# GasSensor.net
KiCad netlist of a schematic drawn in Altium Designer
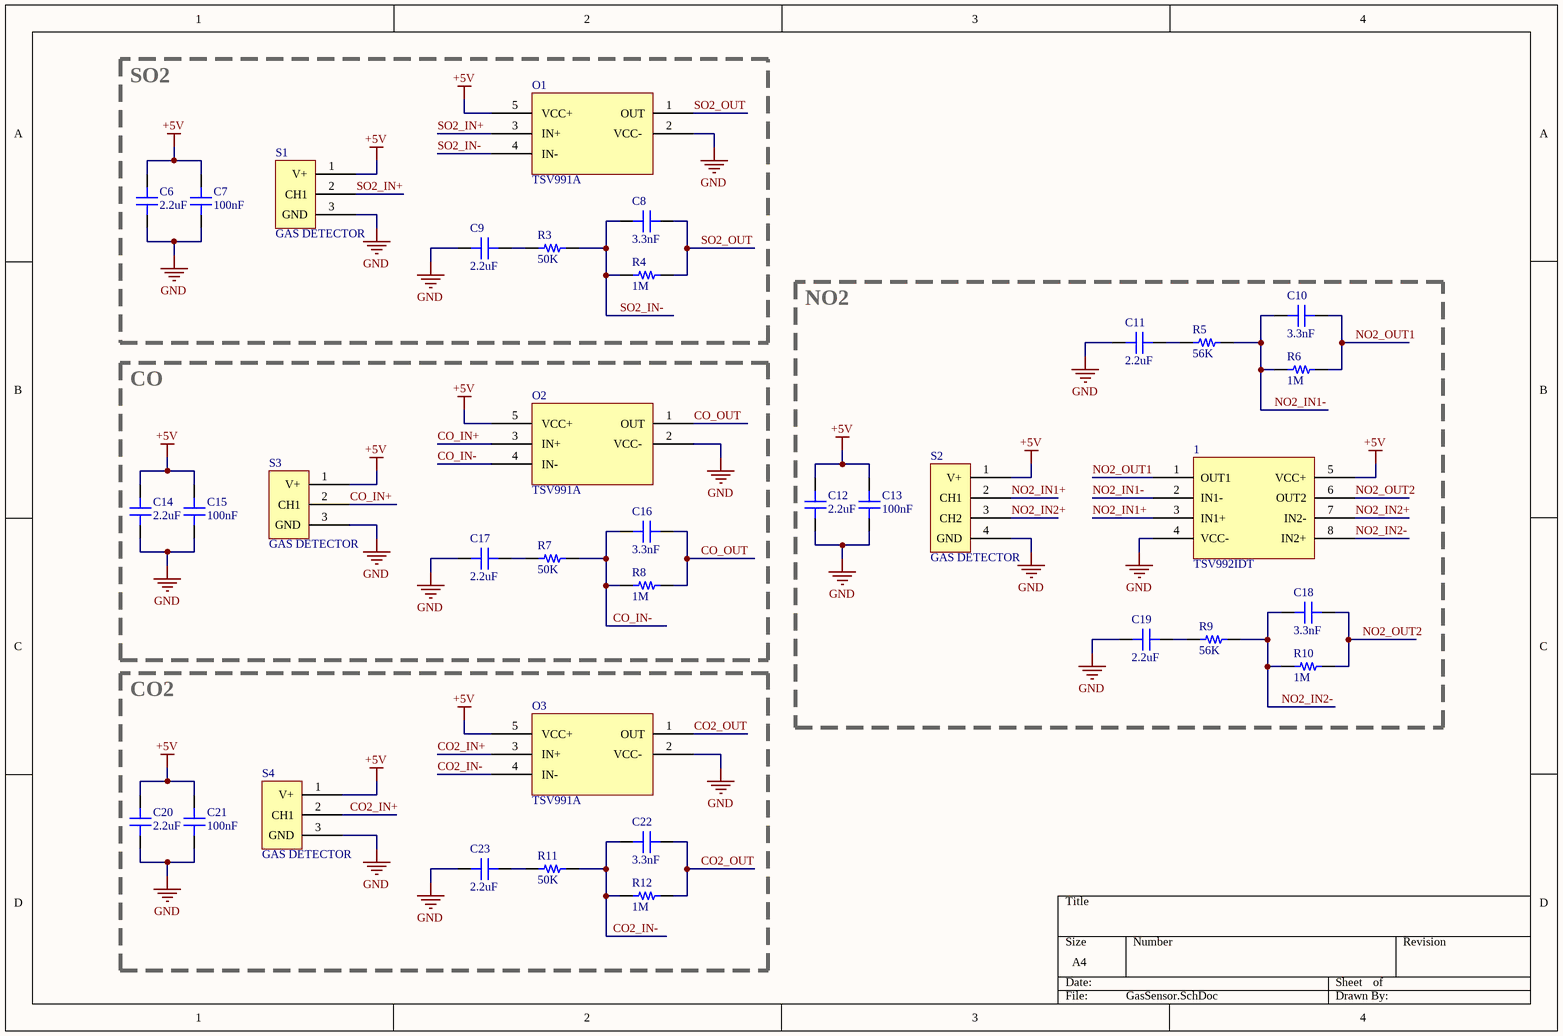
[diagram p0: GasSensor.SchDoc]

(export (version "E")
  (design (tool "Eeschema 10.0.6"))
  (components
    (comp (ref "1")
      (value "TSV992IDT")
      (footprint "SOIC8")
      (description "Operational Amplifiers Op Amps SOIC-8 2 Channel 20 MHz")
      (libsource (lib "hava_kalitesi_olcumu") (part "TSV992IDT"))
    )
    (comp (ref "C6")
      (value "2.2uF")
      (footprint "CAP 0603_1608")
      (description "CERAMİC 1206 SMD")
      (libsource (lib "hava_kalitesi_olcumu") (part "2.2uF"))
    )
    (comp (ref "C7")
      (value "100nF")
      (footprint "CAP 0603_1608")
      (description "CERAMİC 1206 SMD")
      (libsource (lib "hava_kalitesi_olcumu") (part "100nF"))
    )
    (comp (ref "C8")
      (value "3.3nF")
      (footprint "CAP 0603_1608")
      (description "CERAMİC 1206 SMD")
      (libsource (lib "hava_kalitesi_olcumu") (part "3.3nF"))
    )
    (comp (ref "C9")
      (value "2.2uF")
      (footprint "CAP 0603_1608")
      (description "CERAMİC 1206 SMD")
      (libsource (lib "hava_kalitesi_olcumu") (part "2.2uF"))
    )
    (comp (ref "C10")
      (value "3.3nF")
      (footprint "CAP 0603_1608")
      (description "CERAMİC 1206 SMD")
      (libsource (lib "hava_kalitesi_olcumu") (part "3.3nF"))
    )
    (comp (ref "C11")
      (value "2.2uF")
      (footprint "CAP 0603_1608")
      (description "CERAMİC 1206 SMD")
      (libsource (lib "hava_kalitesi_olcumu") (part "2.2uF"))
    )
    (comp (ref "C12")
      (value "2.2uF")
      (footprint "CAP 0603_1608")
      (description "CERAMİC 1206 SMD")
      (libsource (lib "hava_kalitesi_olcumu") (part "2.2uF"))
    )
    (comp (ref "C13")
      (value "100nF")
      (footprint "CAP 0603_1608")
      (description "CERAMİC 1206 SMD")
      (libsource (lib "hava_kalitesi_olcumu") (part "100nF"))
    )
    (comp (ref "C14")
      (value "2.2uF")
      (footprint "CAP 0603_1608")
      (description "CERAMİC 1206 SMD")
      (libsource (lib "hava_kalitesi_olcumu") (part "2.2uF"))
    )
    (comp (ref "C15")
      (value "100nF")
      (footprint "CAP 0603_1608")
      (description "CERAMİC 1206 SMD")
      (libsource (lib "hava_kalitesi_olcumu") (part "100nF"))
    )
    (comp (ref "C16")
      (value "3.3nF")
      (footprint "CAP 0603_1608")
      (description "CERAMİC 1206 SMD")
      (libsource (lib "hava_kalitesi_olcumu") (part "3.3nF"))
    )
    (comp (ref "C17")
      (value "2.2uF")
      (footprint "CAP 0603_1608")
      (description "CERAMİC 1206 SMD")
      (libsource (lib "hava_kalitesi_olcumu") (part "2.2uF"))
    )
    (comp (ref "C18")
      (value "3.3nF")
      (footprint "CAP 0603_1608")
      (description "CERAMİC 1206 SMD")
      (libsource (lib "hava_kalitesi_olcumu") (part "3.3nF"))
    )
    (comp (ref "C19")
      (value "2.2uF")
      (footprint "CAP 0603_1608")
      (description "CERAMİC 1206 SMD")
      (libsource (lib "hava_kalitesi_olcumu") (part "2.2uF"))
    )
    (comp (ref "C20")
      (value "2.2uF")
      (footprint "CAP 0603_1608")
      (description "CERAMİC 1206 SMD")
      (libsource (lib "hava_kalitesi_olcumu") (part "2.2uF"))
    )
    (comp (ref "C21")
      (value "100nF")
      (footprint "CAP 0603_1608")
      (description "CERAMİC 1206 SMD")
      (libsource (lib "hava_kalitesi_olcumu") (part "100nF"))
    )
    (comp (ref "C22")
      (value "3.3nF")
      (footprint "CAP 0603_1608")
      (description "CERAMİC 1206 SMD")
      (libsource (lib "hava_kalitesi_olcumu") (part "3.3nF"))
    )
    (comp (ref "C23")
      (value "2.2uF")
      (footprint "CAP 0603_1608")
      (description "CERAMİC 1206 SMD")
      (libsource (lib "hava_kalitesi_olcumu") (part "2.2uF"))
    )
    (comp (ref "O1")
      (value "TSV991A")
      (footprint "SOT23-5")
      (description "Operational Amplifiers Op Amps SOT23-5 1 Channel 20 MHz")
      (libsource (lib "hava_kalitesi_olcumu") (part "TSV991A"))
    )
    (comp (ref "O2")
      (value "TSV991A")
      (footprint "SOT23-5")
      (description "Operational Amplifiers Op Amps SOT23-5 1 Channel 20 MHz")
      (libsource (lib "hava_kalitesi_olcumu") (part "TSV991A"))
    )
    (comp (ref "O3")
      (value "TSV991A")
      (footprint "SOT23-5")
      (description "Operational Amplifiers Op Amps SOT23-5 1 Channel 20 MHz")
      (libsource (lib "hava_kalitesi_olcumu") (part "TSV991A"))
    )
    (comp (ref "R3")
      (value "50K")
      (footprint "RES 0603_1608")
      (description "SMT RES 1206")
      (libsource (lib "hava_kalitesi_olcumu") (part "50K"))
    )
    (comp (ref "R4")
      (value "1M")
      (footprint "RES 0603_1608")
      (description "SMT RES 1206")
      (libsource (lib "hava_kalitesi_olcumu") (part "1M"))
    )
    (comp (ref "R5")
      (value "56K")
      (footprint "RES 0603_1608")
      (description "SMT RES 1206")
      (libsource (lib "hava_kalitesi_olcumu") (part "56K"))
    )
    (comp (ref "R6")
      (value "1M")
      (footprint "RES 0603_1608")
      (description "SMT RES 1206")
      (libsource (lib "hava_kalitesi_olcumu") (part "1M"))
    )
    (comp (ref "R7")
      (value "50K")
      (footprint "RES 0603_1608")
      (description "SMT RES 1206")
      (libsource (lib "hava_kalitesi_olcumu") (part "50K"))
    )
    (comp (ref "R8")
      (value "1M")
      (footprint "RES 0603_1608")
      (description "SMT RES 1206")
      (libsource (lib "hava_kalitesi_olcumu") (part "1M"))
    )
    (comp (ref "R9")
      (value "56K")
      (footprint "RES 0603_1608")
      (description "SMT RES 1206")
      (libsource (lib "hava_kalitesi_olcumu") (part "56K"))
    )
    (comp (ref "R10")
      (value "1M")
      (footprint "RES 0603_1608")
      (description "SMT RES 1206")
      (libsource (lib "hava_kalitesi_olcumu") (part "1M"))
    )
    (comp (ref "R11")
      (value "50K")
      (footprint "RES 0603_1608")
      (description "SMT RES 1206")
      (libsource (lib "hava_kalitesi_olcumu") (part "50K"))
    )
    (comp (ref "R12")
      (value "1M")
      (footprint "RES 0603_1608")
      (description "SMT RES 1206")
      (libsource (lib "hava_kalitesi_olcumu") (part "1M"))
    )
    (comp (ref "S1")
      (value "GAS DETECTOR")
      (footprint "TO-39 CIRCLE")
      (description "GAS DETECTOR, ANALOG TO-39, GAS")
      (libsource (lib "hava_kalitesi_olcumu") (part "QGC Circle Sensor"))
    )
    (comp (ref "S2")
      (value "GAS DETECTOR")
      (footprint "TO-39 DUAL")
      (description "GAS DETECTOR, ANALOG TO-39, GAS")
      (libsource (lib "hava_kalitesi_olcumu") (part "QGC Dual Sensor"))
    )
    (comp (ref "S3")
      (value "GAS DETECTOR")
      (footprint "TO-39 CIRCLE")
      (description "GAS DETECTOR, ANALOG TO-39, GAS")
      (libsource (lib "hava_kalitesi_olcumu") (part "QGC Circle Sensor"))
    )
    (comp (ref "S4")
      (value "GAS DETECTOR")
      (footprint "TO-39 CIRCLE")
      (description "GAS DETECTOR, ANALOG TO-39, GAS")
      (libsource (lib "hava_kalitesi_olcumu") (part "QGC Circle Sensor"))
    )
  )
  (nets
    (net (code "1") (name "+5V") (class "Default")
      (node (ref "1") (pin "5") (pinfunction "VCC+_5") (pintype "passive"))
      (node (ref "C12") (pin "1") (pinfunction "1_1") (pintype "passive"))
      (node (ref "C13") (pin "2") (pinfunction "2_2") (pintype "passive"))
      (node (ref "C14") (pin "1") (pinfunction "1_1") (pintype "passive"))
      (node (ref "C15") (pin "2") (pinfunction "2_2") (pintype "passive"))
      (node (ref "C20") (pin "1") (pinfunction "1_1") (pintype "passive"))
      (node (ref "C21") (pin "2") (pinfunction "2_2") (pintype "passive"))
      (node (ref "C6") (pin "1") (pinfunction "1_1") (pintype "passive"))
      (node (ref "C7") (pin "2") (pinfunction "2_2") (pintype "passive"))
      (node (ref "O1") (pin "5") (pinfunction "VCC+_5") (pintype "passive"))
      (node (ref "O2") (pin "5") (pinfunction "VCC+_5") (pintype "passive"))
      (node (ref "O3") (pin "5") (pinfunction "VCC+_5") (pintype "passive"))
      (node (ref "S1") (pin "1") (pinfunction "V+_1") (pintype "passive"))
      (node (ref "S2") (pin "1") (pinfunction "V+_1") (pintype "passive"))
      (node (ref "S3") (pin "1") (pinfunction "V+_1") (pintype "passive"))
      (node (ref "S4") (pin "1") (pinfunction "V+_1") (pintype "passive"))
    )
    (net (code "2") (name "/CO2_IN+") (class "Default")
      (node (ref "O3") (pin "3") (pinfunction "IN+_3") (pintype "passive"))
      (node (ref "S4") (pin "2") (pinfunction "CH1_2") (pintype "passive"))
    )
    (net (code "3") (name "/CO2_IN-") (class "Default")
      (node (ref "C22") (pin "1") (pinfunction "1_1") (pintype "passive"))
      (node (ref "O3") (pin "4") (pinfunction "IN-_4") (pintype "passive"))
      (node (ref "R11") (pin "2") (pinfunction "2_2") (pintype "passive"))
      (node (ref "R12") (pin "1") (pinfunction "1_1") (pintype "passive"))
    )
    (net (code "4") (name "/CO2_OUT") (class "Default")
      (node (ref "C22") (pin "2") (pinfunction "2_2") (pintype "passive"))
      (node (ref "O3") (pin "1") (pinfunction "OUT_1") (pintype "passive"))
      (node (ref "R12") (pin "2") (pinfunction "2_2") (pintype "passive"))
    )
    (net (code "5") (name "/CO_IN+") (class "Default")
      (node (ref "O2") (pin "3") (pinfunction "IN+_3") (pintype "passive"))
      (node (ref "S3") (pin "2") (pinfunction "CH1_2") (pintype "passive"))
    )
    (net (code "6") (name "/CO_IN-") (class "Default")
      (node (ref "C16") (pin "1") (pinfunction "1_1") (pintype "passive"))
      (node (ref "O2") (pin "4") (pinfunction "IN-_4") (pintype "passive"))
      (node (ref "R7") (pin "2") (pinfunction "2_2") (pintype "passive"))
      (node (ref "R8") (pin "1") (pinfunction "1_1") (pintype "passive"))
    )
    (net (code "7") (name "/CO_OUT") (class "Default")
      (node (ref "C16") (pin "2") (pinfunction "2_2") (pintype "passive"))
      (node (ref "O2") (pin "1") (pinfunction "OUT_1") (pintype "passive"))
      (node (ref "R8") (pin "2") (pinfunction "2_2") (pintype "passive"))
    )
    (net (code "8") (name "/NO2_IN1+") (class "Default")
      (node (ref "1") (pin "3") (pinfunction "IN1+_3") (pintype "passive"))
      (node (ref "S2") (pin "2") (pinfunction "CH1_2") (pintype "passive"))
    )
    (net (code "9") (name "/NO2_IN1-") (class "Default")
      (node (ref "1") (pin "2") (pinfunction "IN1-_2") (pintype "passive"))
      (node (ref "C10") (pin "1") (pinfunction "1_1") (pintype "passive"))
      (node (ref "R5") (pin "2") (pinfunction "2_2") (pintype "passive"))
      (node (ref "R6") (pin "1") (pinfunction "1_1") (pintype "passive"))
    )
    (net (code "10") (name "/NO2_IN2+") (class "Default")
      (node (ref "1") (pin "7") (pinfunction "IN2-_7") (pintype "passive"))
      (node (ref "S2") (pin "3") (pinfunction "CH2_3") (pintype "passive"))
    )
    (net (code "11") (name "/NO2_IN2-") (class "Default")
      (node (ref "1") (pin "8") (pinfunction "IN2+_8") (pintype "passive"))
      (node (ref "C18") (pin "1") (pinfunction "1_1") (pintype "passive"))
      (node (ref "R10") (pin "1") (pinfunction "1_1") (pintype "passive"))
      (node (ref "R9") (pin "2") (pinfunction "2_2") (pintype "passive"))
    )
    (net (code "12") (name "/NO2_OUT1") (class "Default")
      (node (ref "1") (pin "1") (pinfunction "OUT1_1") (pintype "passive"))
      (node (ref "C10") (pin "2") (pinfunction "2_2") (pintype "passive"))
      (node (ref "R6") (pin "2") (pinfunction "2_2") (pintype "passive"))
    )
    (net (code "13") (name "/NO2_OUT2") (class "Default")
      (node (ref "1") (pin "6") (pinfunction "OUT2_6") (pintype "passive"))
      (node (ref "C18") (pin "2") (pinfunction "2_2") (pintype "passive"))
      (node (ref "R10") (pin "2") (pinfunction "2_2") (pintype "passive"))
    )
    (net (code "14") (name "/SO2_IN+") (class "Default")
      (node (ref "O1") (pin "3") (pinfunction "IN+_3") (pintype "passive"))
      (node (ref "S1") (pin "2") (pinfunction "CH1_2") (pintype "passive"))
    )
    (net (code "15") (name "/SO2_IN-") (class "Default")
      (node (ref "C8") (pin "1") (pinfunction "1_1") (pintype "passive"))
      (node (ref "O1") (pin "4") (pinfunction "IN-_4") (pintype "passive"))
      (node (ref "R3") (pin "2") (pinfunction "2_2") (pintype "passive"))
      (node (ref "R4") (pin "1") (pinfunction "1_1") (pintype "passive"))
    )
    (net (code "16") (name "/SO2_OUT") (class "Default")
      (node (ref "C8") (pin "2") (pinfunction "2_2") (pintype "passive"))
      (node (ref "O1") (pin "1") (pinfunction "OUT_1") (pintype "passive"))
      (node (ref "R4") (pin "2") (pinfunction "2_2") (pintype "passive"))
    )
    (net (code "17") (name "GND") (class "Default")
      (node (ref "1") (pin "4") (pinfunction "VCC-_4") (pintype "passive"))
      (node (ref "C11") (pin "1") (pinfunction "1_1") (pintype "passive"))
      (node (ref "C12") (pin "2") (pinfunction "2_2") (pintype "passive"))
      (node (ref "C13") (pin "1") (pinfunction "1_1") (pintype "passive"))
      (node (ref "C14") (pin "2") (pinfunction "2_2") (pintype "passive"))
      (node (ref "C15") (pin "1") (pinfunction "1_1") (pintype "passive"))
      (node (ref "C17") (pin "1") (pinfunction "1_1") (pintype "passive"))
      (node (ref "C19") (pin "1") (pinfunction "1_1") (pintype "passive"))
      (node (ref "C20") (pin "2") (pinfunction "2_2") (pintype "passive"))
      (node (ref "C21") (pin "1") (pinfunction "1_1") (pintype "passive"))
      (node (ref "C23") (pin "1") (pinfunction "1_1") (pintype "passive"))
      (node (ref "C6") (pin "2") (pinfunction "2_2") (pintype "passive"))
      (node (ref "C7") (pin "1") (pinfunction "1_1") (pintype "passive"))
      (node (ref "C9") (pin "1") (pinfunction "1_1") (pintype "passive"))
      (node (ref "O1") (pin "2") (pinfunction "VCC-_2") (pintype "passive"))
      (node (ref "O2") (pin "2") (pinfunction "VCC-_2") (pintype "passive"))
      (node (ref "O3") (pin "2") (pinfunction "VCC-_2") (pintype "passive"))
      (node (ref "S1") (pin "3") (pinfunction "GND_3") (pintype "passive"))
      (node (ref "S2") (pin "4") (pinfunction "GND_4") (pintype "passive"))
      (node (ref "S3") (pin "3") (pinfunction "GND_3") (pintype "passive"))
      (node (ref "S4") (pin "3") (pinfunction "GND_3") (pintype "passive"))
    )
    (net (code "18") (name "Net-(C9-Pad2)") (class "Default")
      (node (ref "C9") (pin "2") (pinfunction "2_2") (pintype "passive"))
      (node (ref "R3") (pin "1") (pinfunction "1_1") (pintype "passive"))
    )
    (net (code "19") (name "Net-(C11-Pad2)") (class "Default")
      (node (ref "C11") (pin "2") (pinfunction "2_2") (pintype "passive"))
      (node (ref "R5") (pin "1") (pinfunction "1_1") (pintype "passive"))
    )
    (net (code "20") (name "Net-(C17-Pad2)") (class "Default")
      (node (ref "C17") (pin "2") (pinfunction "2_2") (pintype "passive"))
      (node (ref "R7") (pin "1") (pinfunction "1_1") (pintype "passive"))
    )
    (net (code "21") (name "Net-(C19-Pad2)") (class "Default")
      (node (ref "C19") (pin "2") (pinfunction "2_2") (pintype "passive"))
      (node (ref "R9") (pin "1") (pinfunction "1_1") (pintype "passive"))
    )
    (net (code "22") (name "Net-(C23-Pad2)") (class "Default")
      (node (ref "C23") (pin "2") (pinfunction "2_2") (pintype "passive"))
      (node (ref "R11") (pin "1") (pinfunction "1_1") (pintype "passive"))
    )
  )
)
